# arduino_Shield_ABZ_Decoder_V01.net
KiCad netlist of a schematic drawn in EAGLE
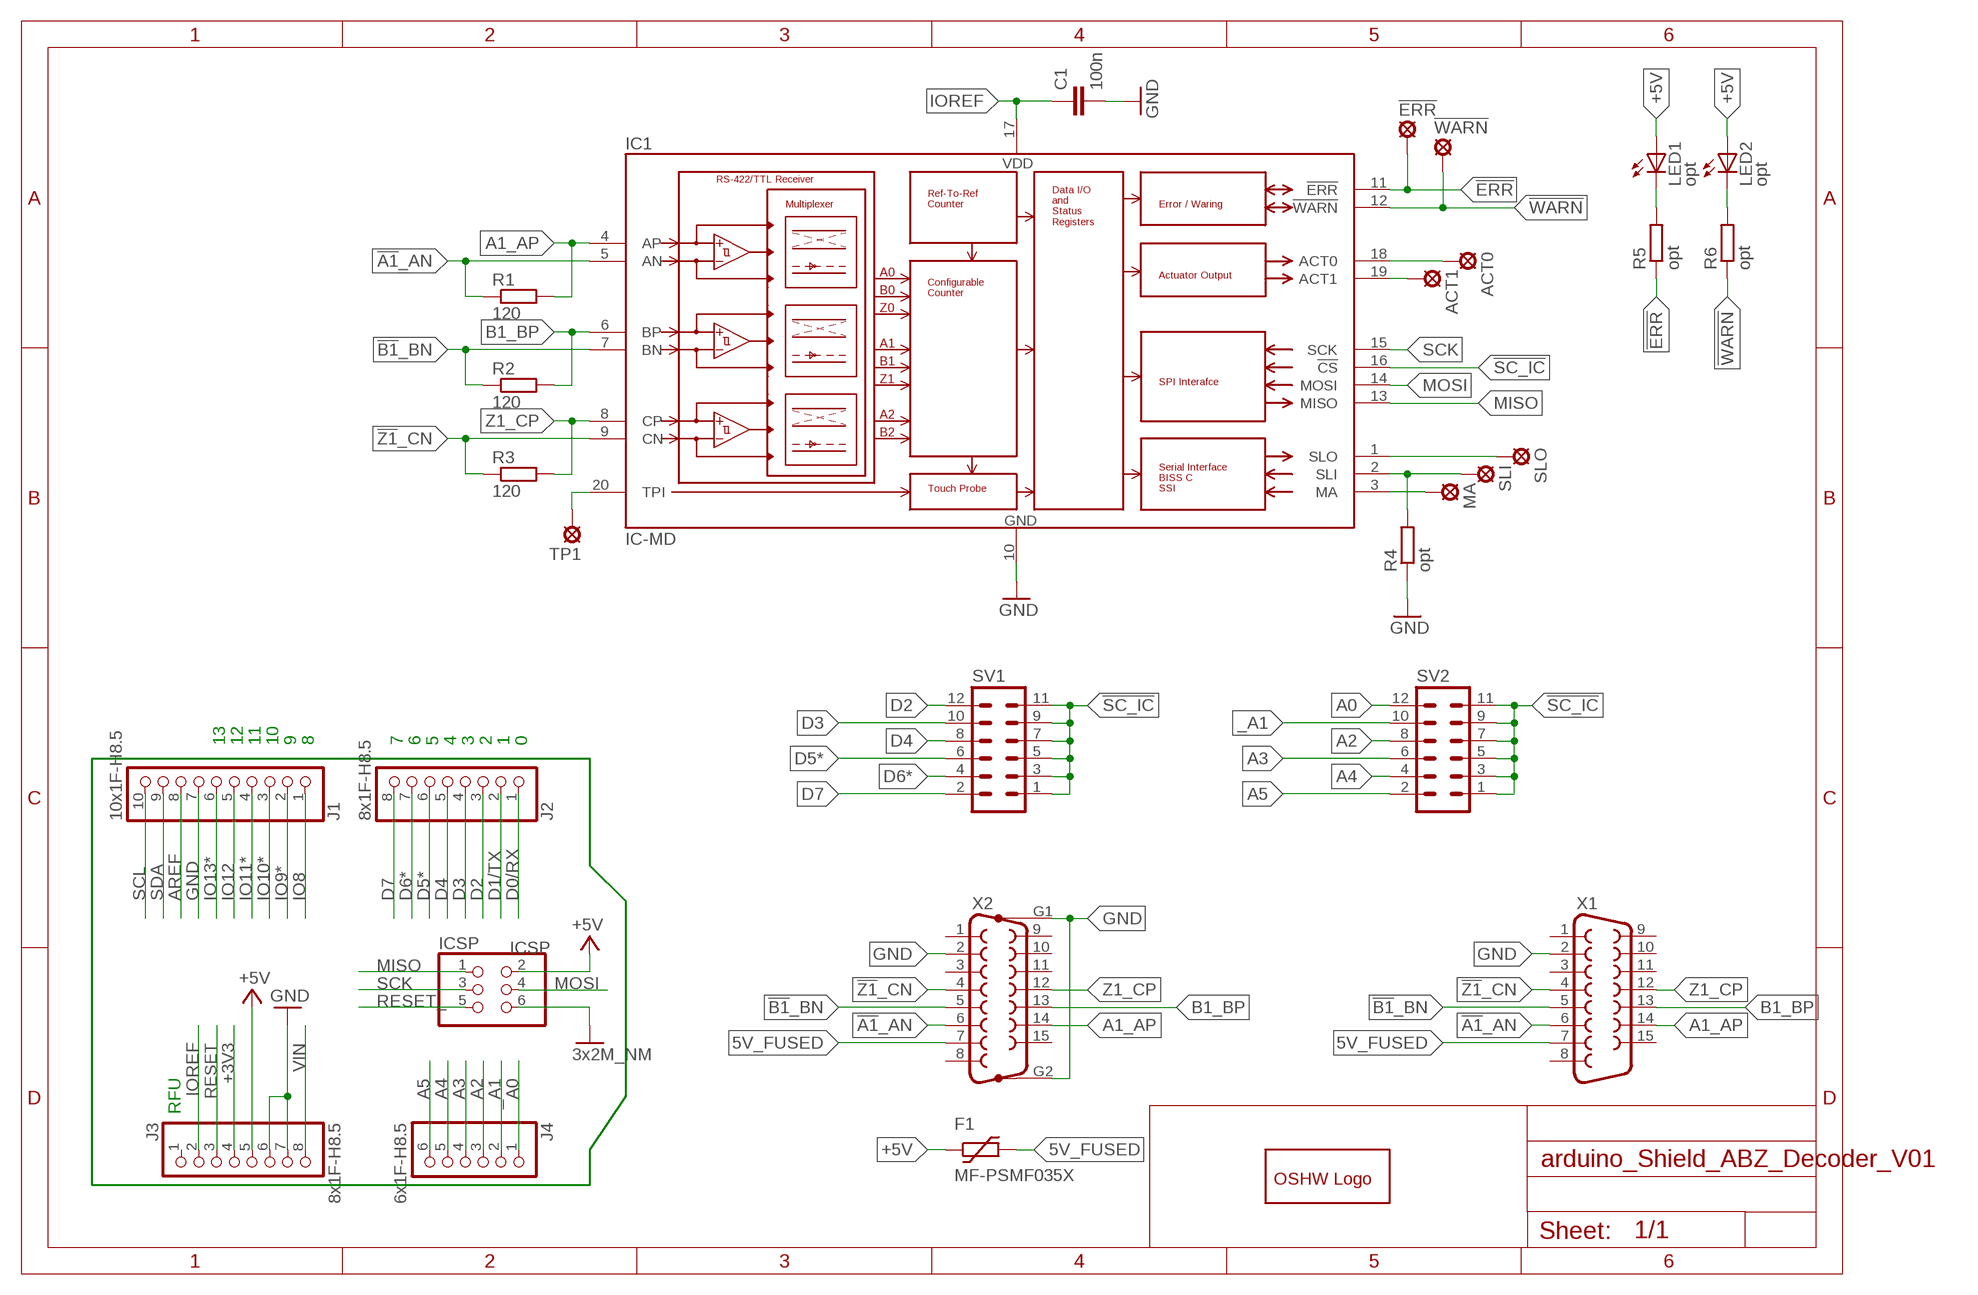
[diagram p0: schematic, sheet 1]

(export (version "E")
  (design (tool "Eeschema 10.0.6"))
  (components
    (comp (ref "!ERR")
      (value "LSP10")
      (footprint "eagle-import:LSP10")
      (libsource (lib "eagle-import") (part "LSP10"))
    )
    (comp (ref "!WARN")
      (value "LSP10")
      (footprint "eagle-import:LSP10")
      (libsource (lib "eagle-import") (part "LSP10"))
    )
    (comp (ref "ACT0")
      (value "LSP10")
      (footprint "eagle-import:LSP10")
      (libsource (lib "eagle-import") (part "LSP10"))
    )
    (comp (ref "ACT1")
      (value "LSP10")
      (footprint "eagle-import:LSP10")
      (libsource (lib "eagle-import") (part "LSP10"))
    )
    (comp (ref "C1")
      (value "100n")
      (footprint "eagle-import:C0805")
      (libsource (lib "eagle-import") (part "C-EUC0805"))
    )
    (comp (ref "F1")
      (value "MF-PSMF035X")
      (footprint "eagle-import:F0805")
      (libsource (lib "eagle-import") (part "MF-PSMFX035"))
    )
    (comp (ref "GOLD_ORB_SM1")
      (value "OSHWLOGOLOGO8MM")
      (footprint "eagle-import:OSHW_8MM")
      (libsource (lib "eagle-import") (part "OSHWLOGOLOGO8MM"))
    )
    (comp (ref "IC1")
      (value "IC-MD")
      (footprint "eagle-import:TSSOP20")
      (fields (field (name "MANUFACTURER") "IC-Haus") (field (name "MPN") "iC-MD TSSOP20"))
      (libsource (lib "eagle-import") (part "IC-MD"))
    )
    (comp (ref "ICSP")
      (value "ICSP")
      (footprint "eagle-import:2X03")
      (libsource (lib "eagle-import") (part "PINHD-2X3"))
    )
    (comp (ref "J1")
      (value "10x1F-H8.5")
      (footprint "eagle-import:1X10")
      (libsource (lib "eagle-import") (part "PINHD-1X10"))
    )
    (comp (ref "J2")
      (value "8x1F-H8.5")
      (footprint "eagle-import:1X08")
      (libsource (lib "eagle-import") (part "PINHD-1X8"))
    )
    (comp (ref "J3")
      (value "8x1F-H8.5")
      (footprint "eagle-import:1X08")
      (libsource (lib "eagle-import") (part "PINHD-1X8"))
    )
    (comp (ref "J4")
      (value "6x1F-H8.5")
      (footprint "eagle-import:1X06")
      (libsource (lib "eagle-import") (part "PINHD-1X6"))
    )
    (comp (ref "LED1")
      (value "opt")
      (footprint "eagle-import:LED3MM")
      (libsource (lib "eagle-import") (part "LED3MM"))
    )
    (comp (ref "LED2")
      (value "opt")
      (footprint "eagle-import:LED3MM")
      (libsource (lib "eagle-import") (part "LED3MM"))
    )
    (comp (ref "MA")
      (value "LSP10")
      (footprint "eagle-import:LSP10")
      (libsource (lib "eagle-import") (part "LSP10"))
    )
    (comp (ref "R1")
      (value "120")
      (footprint "eagle-import:M1206")
      (libsource (lib "eagle-import") (part "R-EU_M1206"))
    )
    (comp (ref "R2")
      (value "120")
      (footprint "eagle-import:M1206")
      (libsource (lib "eagle-import") (part "R-EU_M1206"))
    )
    (comp (ref "R3")
      (value "120")
      (footprint "eagle-import:M1206")
      (libsource (lib "eagle-import") (part "R-EU_M1206"))
    )
    (comp (ref "R4")
      (value "opt")
      (footprint "eagle-import:M1206")
      (libsource (lib "eagle-import") (part "R-EU_M1206"))
    )
    (comp (ref "R5")
      (value "opt")
      (footprint "eagle-import:M1206")
      (libsource (lib "eagle-import") (part "R-EU_M1206"))
    )
    (comp (ref "R6")
      (value "opt")
      (footprint "eagle-import:M1206")
      (libsource (lib "eagle-import") (part "R-EU_M1206"))
    )
    (comp (ref "SLI")
      (value "LSP10")
      (footprint "eagle-import:LSP10")
      (libsource (lib "eagle-import") (part "LSP10"))
    )
    (comp (ref "SLO")
      (value "LSP10")
      (footprint "eagle-import:LSP10")
      (libsource (lib "eagle-import") (part "LSP10"))
    )
    (comp (ref "SV1")
      (value "MA06-2")
      (footprint "eagle-import:MA06-2")
      (libsource (lib "eagle-import") (part "MA06-2"))
    )
    (comp (ref "SV2")
      (value "MA06-2")
      (footprint "eagle-import:MA06-2")
      (libsource (lib "eagle-import") (part "MA06-2"))
    )
    (comp (ref "TP1")
      (value "LSP10")
      (footprint "eagle-import:LSP10")
      (libsource (lib "eagle-import") (part "LSP10"))
    )
    (comp (ref "X1")
      (value "F15D")
      (footprint "eagle-import:F15D")
      (libsource (lib "eagle-import") (part "F15D"))
    )
    (comp (ref "X2")
      (value "F15HP")
      (footprint "eagle-import:F15HP")
      (libsource (lib "eagle-import") (part "con-subd_F15HP"))
    )
  )
  (nets
    (net (code "1") (name "+5V") (class "Default")
      (node (ref "F1") (pin "1") (pinfunction "1_1") (pintype "passive"))
      (node (ref "ICSP") (pin "2") (pinfunction "2_2") (pintype "passive"))
      (node (ref "J3") (pin "5") (pinfunction "5_5") (pintype "passive"))
      (node (ref "LED1") (pin "A") (pinfunction "A_A") (pintype "passive"))
      (node (ref "LED2") (pin "A") (pinfunction "A_A") (pintype "passive"))
    )
    (net (code "2") (name "/+3V3") (class "Default")
      (node (ref "J3") (pin "4") (pinfunction "4_4") (pintype "passive"))
    )
    (net (code "3") (name "/AREF") (class "Default")
      (node (ref "J1") (pin "8") (pinfunction "8_8") (pintype "passive"))
    )
    (net (code "4") (name "/D0{slash}RX") (class "Default")
      (node (ref "J2") (pin "1") (pinfunction "1_1") (pintype "passive"))
    )
    (net (code "5") (name "/D1{slash}TX") (class "Default")
      (node (ref "J2") (pin "2") (pinfunction "2_2") (pintype "passive"))
    )
    (net (code "6") (name "/IO8") (class "Default")
      (node (ref "J1") (pin "1") (pinfunction "1_1") (pintype "passive"))
    )
    (net (code "7") (name "/IO9*") (class "Default")
      (node (ref "J1") (pin "2") (pinfunction "2_2") (pintype "passive"))
    )
    (net (code "8") (name "/IO10*") (class "Default")
      (node (ref "J1") (pin "3") (pinfunction "3_3") (pintype "passive"))
    )
    (net (code "9") (name "/IO11*") (class "Default")
      (node (ref "J1") (pin "4") (pinfunction "4_4") (pintype "passive"))
    )
    (net (code "10") (name "/IO12") (class "Default")
      (node (ref "J1") (pin "5") (pinfunction "5_5") (pintype "passive"))
    )
    (net (code "11") (name "/IO13*") (class "Default")
      (node (ref "J1") (pin "6") (pinfunction "6_6") (pintype "passive"))
    )
    (net (code "12") (name "/RESET") (class "Default")
      (node (ref "J3") (pin "3") (pinfunction "3_3") (pintype "passive"))
    )
    (net (code "13") (name "/RESET_") (class "Default")
      (node (ref "ICSP") (pin "5") (pinfunction "5_5") (pintype "passive"))
    )
    (net (code "14") (name "/SCL") (class "Default")
      (node (ref "J1") (pin "10") (pinfunction "10_10") (pintype "passive"))
    )
    (net (code "15") (name "/SDA") (class "Default")
      (node (ref "J1") (pin "9") (pinfunction "9_9") (pintype "passive"))
    )
    (net (code "16") (name "/VIN") (class "Default")
      (node (ref "J3") (pin "8") (pinfunction "8_8") (pintype "passive"))
    )
    (net (code "17") (name "/~{A1}_AN") (class "Default")
      (node (ref "IC1") (pin "5") (pinfunction "AN_5") (pintype "input"))
      (node (ref "R1") (pin "1") (pinfunction "1_1") (pintype "passive"))
      (node (ref "X1") (pin "6") (pinfunction "6_6") (pintype "passive"))
      (node (ref "X2") (pin "6") (pinfunction "6_6") (pintype "passive"))
    )
    (net (code "18") (name "/~{B1}_BN") (class "Default")
      (node (ref "IC1") (pin "7") (pinfunction "BN_7") (pintype "input"))
      (node (ref "R2") (pin "1") (pinfunction "1_1") (pintype "passive"))
      (node (ref "X1") (pin "5") (pinfunction "5_5") (pintype "passive"))
      (node (ref "X2") (pin "5") (pinfunction "5_5") (pintype "passive"))
    )
    (net (code "19") (name "/~{ERR}") (class "Default")
      (node (ref "!ERR") (pin "MP") (pinfunction "MP_MP") (pintype "passive"))
      (node (ref "IC1") (pin "11") (pinfunction "~{ERR}_11") (pintype "bidirectional"))
      (node (ref "R5") (pin "1") (pinfunction "1_1") (pintype "passive"))
    )
    (net (code "20") (name "/~{SC_IC}") (class "Default")
      (node (ref "IC1") (pin "16") (pinfunction "~{CS}_16") (pintype "input"))
      (node (ref "SV1") (pin "1") (pinfunction "1_1") (pintype "passive"))
      (node (ref "SV1") (pin "11") (pinfunction "11_11") (pintype "passive"))
      (node (ref "SV1") (pin "3") (pinfunction "3_3") (pintype "passive"))
      (node (ref "SV1") (pin "5") (pinfunction "5_5") (pintype "passive"))
      (node (ref "SV1") (pin "7") (pinfunction "7_7") (pintype "passive"))
      (node (ref "SV1") (pin "9") (pinfunction "9_9") (pintype "passive"))
      (node (ref "SV2") (pin "1") (pinfunction "1_1") (pintype "passive"))
      (node (ref "SV2") (pin "11") (pinfunction "11_11") (pintype "passive"))
      (node (ref "SV2") (pin "3") (pinfunction "3_3") (pintype "passive"))
      (node (ref "SV2") (pin "5") (pinfunction "5_5") (pintype "passive"))
      (node (ref "SV2") (pin "7") (pinfunction "7_7") (pintype "passive"))
      (node (ref "SV2") (pin "9") (pinfunction "9_9") (pintype "passive"))
    )
    (net (code "21") (name "/~{WARN}") (class "Default")
      (node (ref "!WARN") (pin "MP") (pinfunction "MP_MP") (pintype "passive"))
      (node (ref "IC1") (pin "12") (pinfunction "~{WARN}_12") (pintype "bidirectional"))
      (node (ref "R6") (pin "1") (pinfunction "1_1") (pintype "passive"))
    )
    (net (code "22") (name "/~{Z1}_CN") (class "Default")
      (node (ref "IC1") (pin "9") (pinfunction "CN_9") (pintype "input"))
      (node (ref "R3") (pin "1") (pinfunction "1_1") (pintype "passive"))
      (node (ref "X1") (pin "4") (pinfunction "4_4") (pintype "passive"))
      (node (ref "X2") (pin "4") (pinfunction "4_4") (pintype "passive"))
    )
    (net (code "23") (name "5V_FUSED") (class "Default")
      (node (ref "F1") (pin "2") (pinfunction "2_2") (pintype "passive"))
      (node (ref "X1") (pin "7") (pinfunction "7_7") (pintype "passive"))
      (node (ref "X2") (pin "7") (pinfunction "7_7") (pintype "passive"))
    )
    (net (code "24") (name "A0") (class "Default")
      (node (ref "J4") (pin "1") (pinfunction "1_1") (pintype "passive"))
      (node (ref "SV2") (pin "12") (pinfunction "12_12") (pintype "passive"))
    )
    (net (code "25") (name "A1_AP") (class "Default")
      (node (ref "IC1") (pin "4") (pinfunction "AP_4") (pintype "input"))
      (node (ref "R1") (pin "2") (pinfunction "2_2") (pintype "passive"))
      (node (ref "X1") (pin "14") (pinfunction "14_14") (pintype "passive"))
      (node (ref "X2") (pin "14") (pinfunction "14_14") (pintype "passive"))
    )
    (net (code "26") (name "A2") (class "Default")
      (node (ref "J4") (pin "3") (pinfunction "3_3") (pintype "passive"))
      (node (ref "SV2") (pin "8") (pinfunction "8_8") (pintype "passive"))
    )
    (net (code "27") (name "A3") (class "Default")
      (node (ref "J4") (pin "4") (pinfunction "4_4") (pintype "passive"))
      (node (ref "SV2") (pin "6") (pinfunction "6_6") (pintype "passive"))
    )
    (net (code "28") (name "A4") (class "Default")
      (node (ref "J4") (pin "5") (pinfunction "5_5") (pintype "passive"))
      (node (ref "SV2") (pin "4") (pinfunction "4_4") (pintype "passive"))
    )
    (net (code "29") (name "A5") (class "Default")
      (node (ref "J4") (pin "6") (pinfunction "6_6") (pintype "passive"))
      (node (ref "SV2") (pin "2") (pinfunction "2_2") (pintype "passive"))
    )
    (net (code "30") (name "B1_BP") (class "Default")
      (node (ref "IC1") (pin "6") (pinfunction "BP_6") (pintype "input"))
      (node (ref "R2") (pin "2") (pinfunction "2_2") (pintype "passive"))
      (node (ref "X1") (pin "13") (pinfunction "13_13") (pintype "passive"))
      (node (ref "X2") (pin "13") (pinfunction "13_13") (pintype "passive"))
    )
    (net (code "31") (name "D2") (class "Default")
      (node (ref "J2") (pin "3") (pinfunction "3_3") (pintype "passive"))
      (node (ref "SV1") (pin "12") (pinfunction "12_12") (pintype "passive"))
    )
    (net (code "32") (name "D3") (class "Default")
      (node (ref "J2") (pin "4") (pinfunction "4_4") (pintype "passive"))
      (node (ref "SV1") (pin "10") (pinfunction "10_10") (pintype "passive"))
    )
    (net (code "33") (name "D4") (class "Default")
      (node (ref "J2") (pin "5") (pinfunction "5_5") (pintype "passive"))
      (node (ref "SV1") (pin "8") (pinfunction "8_8") (pintype "passive"))
    )
    (net (code "34") (name "D5*") (class "Default")
      (node (ref "J2") (pin "6") (pinfunction "6_6") (pintype "passive"))
      (node (ref "SV1") (pin "6") (pinfunction "6_6") (pintype "passive"))
    )
    (net (code "35") (name "D6*") (class "Default")
      (node (ref "J2") (pin "7") (pinfunction "7_7") (pintype "passive"))
      (node (ref "SV1") (pin "4") (pinfunction "4_4") (pintype "passive"))
    )
    (net (code "36") (name "D7") (class "Default")
      (node (ref "J2") (pin "8") (pinfunction "8_8") (pintype "passive"))
      (node (ref "SV1") (pin "2") (pinfunction "2_2") (pintype "passive"))
    )
    (net (code "37") (name "GND") (class "Default")
      (node (ref "C1") (pin "2") (pinfunction "2_2") (pintype "passive"))
      (node (ref "IC1") (pin "10") (pinfunction "GND_10") (pintype "power_in"))
      (node (ref "ICSP") (pin "6") (pinfunction "6_6") (pintype "passive"))
      (node (ref "J1") (pin "7") (pinfunction "7_7") (pintype "passive"))
      (node (ref "J3") (pin "6") (pinfunction "6_6") (pintype "passive"))
      (node (ref "J3") (pin "7") (pinfunction "7_7") (pintype "passive"))
      (node (ref "R4") (pin "1") (pinfunction "1_1") (pintype "passive"))
      (node (ref "X1") (pin "2") (pinfunction "2_2") (pintype "passive"))
      (node (ref "X2") (pin "2") (pinfunction "2_2") (pintype "passive"))
      (node (ref "X2") (pin "G1") (pinfunction "G1_G1") (pintype "passive"))
      (node (ref "X2") (pin "G2") (pinfunction "G2_G2") (pintype "passive"))
    )
    (net (code "38") (name "IOREF") (class "Default")
      (node (ref "C1") (pin "1") (pinfunction "1_1") (pintype "passive"))
      (node (ref "IC1") (pin "17") (pinfunction "VDD_17") (pintype "power_in"))
      (node (ref "J3") (pin "2") (pinfunction "2_2") (pintype "passive"))
    )
    (net (code "39") (name "MISO") (class "Default")
      (node (ref "IC1") (pin "13") (pinfunction "MISO_13") (pintype "tri_state"))
      (node (ref "ICSP") (pin "1") (pinfunction "1_1") (pintype "passive"))
    )
    (net (code "40") (name "MOSI") (class "Default")
      (node (ref "IC1") (pin "14") (pinfunction "MOSI_14") (pintype "input"))
      (node (ref "ICSP") (pin "4") (pinfunction "4_4") (pintype "passive"))
    )
    (net (code "41") (name "Net-(IC1-ACT0)") (class "Default")
      (node (ref "ACT0") (pin "MP") (pinfunction "MP_MP") (pintype "passive"))
      (node (ref "IC1") (pin "18") (pinfunction "ACT0_18") (pintype "output"))
    )
    (net (code "42") (name "Net-(IC1-ACT1)") (class "Default")
      (node (ref "ACT1") (pin "MP") (pinfunction "MP_MP") (pintype "passive"))
      (node (ref "IC1") (pin "19") (pinfunction "ACT1_19") (pintype "output"))
    )
    (net (code "43") (name "Net-(IC1-MA)") (class "Default")
      (node (ref "IC1") (pin "3") (pinfunction "MA_3") (pintype "input"))
      (node (ref "MA") (pin "MP") (pinfunction "MP_MP") (pintype "passive"))
    )
    (net (code "44") (name "Net-(IC1-SLI)") (class "Default")
      (node (ref "IC1") (pin "2") (pinfunction "SLI_2") (pintype "input"))
      (node (ref "R4") (pin "2") (pinfunction "2_2") (pintype "passive"))
      (node (ref "SLI") (pin "MP") (pinfunction "MP_MP") (pintype "passive"))
    )
    (net (code "45") (name "Net-(IC1-SLO)") (class "Default")
      (node (ref "IC1") (pin "1") (pinfunction "SLO_1") (pintype "output"))
      (node (ref "SLO") (pin "MP") (pinfunction "MP_MP") (pintype "passive"))
    )
    (net (code "46") (name "Net-(IC1-TPI)") (class "Default")
      (node (ref "IC1") (pin "20") (pinfunction "TPI_20") (pintype "input"))
      (node (ref "TP1") (pin "MP") (pinfunction "MP_MP") (pintype "passive"))
    )
    (net (code "47") (name "Net-(LED1-C)") (class "Default")
      (node (ref "LED1") (pin "K") (pinfunction "C_K") (pintype "passive"))
      (node (ref "R5") (pin "2") (pinfunction "2_2") (pintype "passive"))
    )
    (net (code "48") (name "Net-(LED2-C)") (class "Default")
      (node (ref "LED2") (pin "K") (pinfunction "C_K") (pintype "passive"))
      (node (ref "R6") (pin "2") (pinfunction "2_2") (pintype "passive"))
    )
    (net (code "49") (name "SCK") (class "Default")
      (node (ref "IC1") (pin "15") (pinfunction "SCK_15") (pintype "input"))
      (node (ref "ICSP") (pin "3") (pinfunction "3_3") (pintype "passive"))
    )
    (net (code "50") (name "Z1_CP") (class "Default")
      (node (ref "IC1") (pin "8") (pinfunction "CP_8") (pintype "input"))
      (node (ref "R3") (pin "2") (pinfunction "2_2") (pintype "passive"))
      (node (ref "X1") (pin "12") (pinfunction "12_12") (pintype "passive"))
      (node (ref "X2") (pin "12") (pinfunction "12_12") (pintype "passive"))
    )
    (net (code "51") (name "_A1") (class "Default")
      (node (ref "J4") (pin "2") (pinfunction "2_2") (pintype "passive"))
      (node (ref "SV2") (pin "10") (pinfunction "10_10") (pintype "passive"))
    )
    (net (code "52") (name "unconnected-(J3-Pad1)") (class "Default")
      (node (ref "J3") (pin "1") (pinfunction "1_1") (pintype "passive"))
    )
    (net (code "53") (name "unconnected-(X1-Pad1)") (class "Default")
      (node (ref "X1") (pin "1") (pinfunction "1_1") (pintype "passive"))
    )
    (net (code "54") (name "unconnected-(X1-Pad3)") (class "Default")
      (node (ref "X1") (pin "3") (pinfunction "3_3") (pintype "passive"))
    )
    (net (code "55") (name "unconnected-(X1-Pad8)") (class "Default")
      (node (ref "X1") (pin "8") (pinfunction "8_8") (pintype "passive"))
    )
    (net (code "56") (name "unconnected-(X1-Pad9)") (class "Default")
      (node (ref "X1") (pin "9") (pinfunction "9_9") (pintype "passive"))
    )
    (net (code "57") (name "unconnected-(X1-Pad10)") (class "Default")
      (node (ref "X1") (pin "10") (pinfunction "10_10") (pintype "passive"))
    )
    (net (code "58") (name "unconnected-(X1-Pad11)") (class "Default")
      (node (ref "X1") (pin "11") (pinfunction "11_11") (pintype "passive"))
    )
    (net (code "59") (name "unconnected-(X1-Pad15)") (class "Default")
      (node (ref "X1") (pin "15") (pinfunction "15_15") (pintype "passive"))
    )
    (net (code "60") (name "unconnected-(X2-Pad1)") (class "Default")
      (node (ref "X2") (pin "1") (pinfunction "1_1") (pintype "passive"))
    )
    (net (code "61") (name "unconnected-(X2-Pad3)") (class "Default")
      (node (ref "X2") (pin "3") (pinfunction "3_3") (pintype "passive"))
    )
    (net (code "62") (name "unconnected-(X2-Pad8)") (class "Default")
      (node (ref "X2") (pin "8") (pinfunction "8_8") (pintype "passive"))
    )
    (net (code "63") (name "unconnected-(X2-Pad9)") (class "Default")
      (node (ref "X2") (pin "9") (pinfunction "9_9") (pintype "passive"))
    )
    (net (code "64") (name "unconnected-(X2-Pad10)") (class "Default")
      (node (ref "X2") (pin "10") (pinfunction "10_10") (pintype "passive"))
    )
    (net (code "65") (name "unconnected-(X2-Pad11)") (class "Default")
      (node (ref "X2") (pin "11") (pinfunction "11_11") (pintype "passive"))
    )
    (net (code "66") (name "unconnected-(X2-Pad15)") (class "Default")
      (node (ref "X2") (pin "15") (pinfunction "15_15") (pintype "passive"))
    )
  )
)
